# slave_board.net
KiCad netlist of a schematic drawn in EAGLE
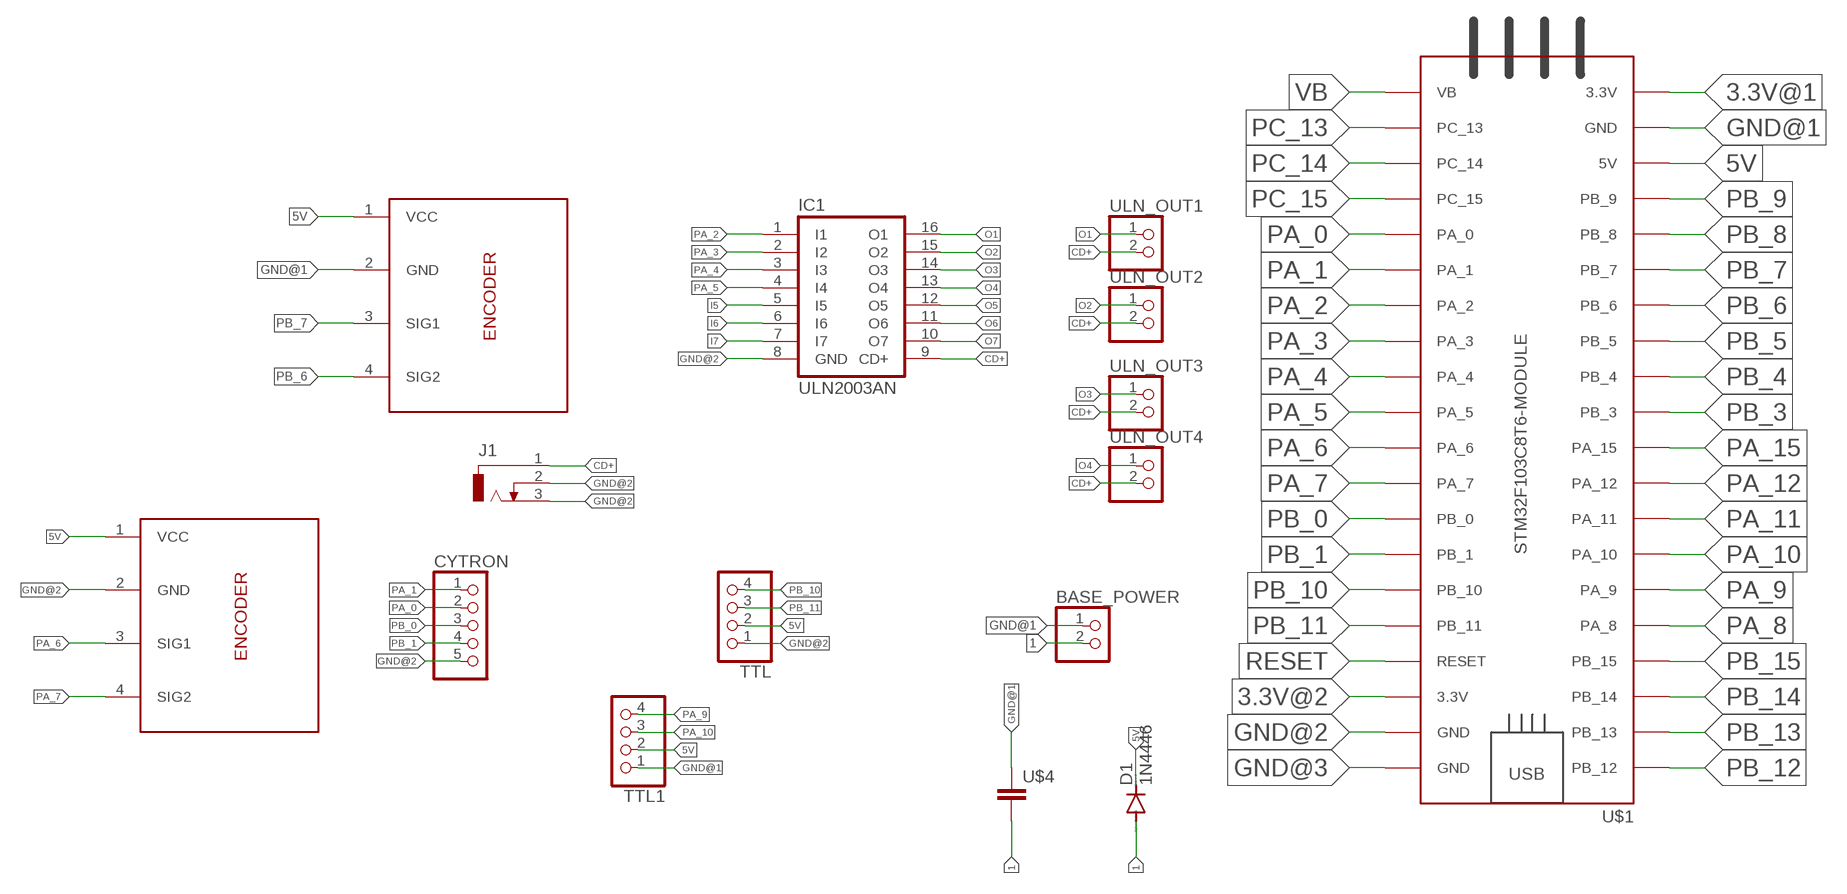
[diagram p0: schematic, sheet 1]

(export (version "E")
  (design (tool "Eeschema 10.0.6"))
  (components
    (comp (ref "BASE_POWER")
      (value "PINHD-2_DATA")
      (footprint "eagle-import:1X02_DATA")
      (libsource (lib "eagle-import") (part "PINHD-2_DATA"))
    )
    (comp (ref "CYTRON")
      (value "PINHD-5_DATA")
      (footprint "eagle-import:1X05_DATA")
      (libsource (lib "eagle-import") (part "PINHD-5_DATA"))
    )
    (comp (ref "D1")
      (value "1N4446")
      (footprint "eagle-import:DO35-10")
      (libsource (lib "eagle-import") (part "1N4446"))
    )
    (comp (ref "IC1")
      (value "ULN2003AN")
      (footprint "eagle-import:DIL16")
      (libsource (lib "eagle-import") (part "ULN2003AN"))
    )
    (comp (ref "J1")
      (value "CON_JACK")
      (footprint "eagle-import:DCJ0303")
      (libsource (lib "eagle-import") (part "CON_JACK"))
    )
    (comp (ref "TTL")
      (value "PINHD-4_DATA")
      (footprint "eagle-import:1X04_DATA")
      (libsource (lib "eagle-import") (part "PINHD-4_DATA"))
    )
    (comp (ref "TTL1")
      (value "PINHD-4_DATA")
      (footprint "eagle-import:1X04_DATA")
      (libsource (lib "eagle-import") (part "PINHD-4_DATA"))
    )
    (comp (ref "U$1")
      (value "STM32F103C8T6-MODULE")
      (footprint "eagle-import:STM32F103C8T6-MODULE")
      (libsource (lib "eagle-import") (part "STM32F103C8T6-MODULE"))
    )
    (comp (ref "U$2")
      (value "ENCODER")
      (footprint "eagle-import:1X04_DATA")
      (libsource (lib "eagle-import") (part "ENCODER"))
    )
    (comp (ref "U$3")
      (value "ENCODER")
      (footprint "eagle-import:1X04_DATA")
      (libsource (lib "eagle-import") (part "ENCODER"))
    )
    (comp (ref "U$4")
      (value "CAPACITOR")
      (footprint "eagle-import:C025-025X050")
      (libsource (lib "eagle-import") (part "CAPACITOR"))
    )
    (comp (ref "ULN_OUT1")
      (value "PINHD-2_DATA")
      (footprint "eagle-import:1X02_DATA")
      (libsource (lib "eagle-import") (part "PINHD-2_DATA"))
    )
    (comp (ref "ULN_OUT2")
      (value "PINHD-2_DATA")
      (footprint "eagle-import:1X02_DATA")
      (libsource (lib "eagle-import") (part "PINHD-2_DATA"))
    )
    (comp (ref "ULN_OUT3")
      (value "PINHD-2_DATA")
      (footprint "eagle-import:1X02_DATA")
      (libsource (lib "eagle-import") (part "PINHD-2_DATA"))
    )
    (comp (ref "ULN_OUT4")
      (value "PINHD-2_DATA")
      (footprint "eagle-import:1X02_DATA")
      (libsource (lib "eagle-import") (part "PINHD-2_DATA"))
    )
  )
  (nets
    (net (code "1") (name "1") (class "Default")
      (node (ref "BASE_POWER") (pin "2") (pinfunction "2_2") (pintype "passive"))
      (node (ref "D1") (pin "A") (pinfunction "A_A") (pintype "passive"))
      (node (ref "U$4") (pin "2") (pinfunction "2_2") (pintype "passive"))
    )
    (net (code "2") (name "3.3V@1") (class "Default")
      (node (ref "U$1") (pin "3.3V_1") (pinfunction "3.3V_3.3V_1") (pintype "bidirectional"))
    )
    (net (code "3") (name "3.3V@2") (class "Default")
      (node (ref "U$1") (pin "3.3V_2") (pinfunction "3.3V_3.3V_2") (pintype "bidirectional"))
    )
    (net (code "4") (name "5V") (class "Default")
      (node (ref "D1") (pin "C") (pinfunction "C_C") (pintype "passive"))
      (node (ref "TTL") (pin "2") (pinfunction "2_2") (pintype "passive"))
      (node (ref "TTL1") (pin "2") (pinfunction "2_2") (pintype "passive"))
      (node (ref "U$1") (pin "5V") (pinfunction "5V_5V") (pintype "bidirectional"))
      (node (ref "U$2") (pin "1") (pinfunction "VCC_1") (pintype "bidirectional"))
      (node (ref "U$3") (pin "1") (pinfunction "VCC_1") (pintype "bidirectional"))
    )
    (net (code "5") (name "CD+") (class "Default")
      (node (ref "IC1") (pin "9") (pinfunction "CD+_9") (pintype "passive"))
      (node (ref "J1") (pin "1") (pinfunction "1_1") (pintype "passive"))
      (node (ref "ULN_OUT1") (pin "2") (pinfunction "2_2") (pintype "passive"))
      (node (ref "ULN_OUT2") (pin "2") (pinfunction "2_2") (pintype "passive"))
      (node (ref "ULN_OUT3") (pin "2") (pinfunction "2_2") (pintype "passive"))
      (node (ref "ULN_OUT4") (pin "2") (pinfunction "2_2") (pintype "passive"))
    )
    (net (code "6") (name "GND@1") (class "Default")
      (node (ref "BASE_POWER") (pin "1") (pinfunction "1_1") (pintype "passive"))
      (node (ref "TTL1") (pin "1") (pinfunction "1_1") (pintype "passive"))
      (node (ref "U$1") (pin "GND_1") (pinfunction "GND_GND_1") (pintype "bidirectional"))
      (node (ref "U$3") (pin "2") (pinfunction "GND_2") (pintype "bidirectional"))
      (node (ref "U$4") (pin "1") (pinfunction "1_1") (pintype "passive"))
    )
    (net (code "7") (name "GND@2") (class "Default")
      (node (ref "CYTRON") (pin "5") (pinfunction "5_5") (pintype "passive"))
      (node (ref "IC1") (pin "8") (pinfunction "GND_8") (pintype "power_in"))
      (node (ref "J1") (pin "2") (pinfunction "2_2") (pintype "passive"))
      (node (ref "J1") (pin "3") (pinfunction "3_3") (pintype "passive"))
      (node (ref "TTL") (pin "1") (pinfunction "1_1") (pintype "passive"))
      (node (ref "U$1") (pin "GND_2") (pinfunction "GND_GND_2") (pintype "bidirectional"))
      (node (ref "U$2") (pin "2") (pinfunction "GND_2") (pintype "bidirectional"))
    )
    (net (code "8") (name "GND@3") (class "Default")
      (node (ref "U$1") (pin "GND_3") (pinfunction "GND_GND_3") (pintype "power_in"))
    )
    (net (code "9") (name "I5") (class "Default")
      (node (ref "IC1") (pin "5") (pinfunction "I5_5") (pintype "input"))
    )
    (net (code "10") (name "I6") (class "Default")
      (node (ref "IC1") (pin "6") (pinfunction "I6_6") (pintype "input"))
    )
    (net (code "11") (name "I7") (class "Default")
      (node (ref "IC1") (pin "7") (pinfunction "I7_7") (pintype "input"))
    )
    (net (code "12") (name "O1") (class "Default")
      (node (ref "IC1") (pin "16") (pinfunction "O1_16") (pintype "open_collector"))
      (node (ref "ULN_OUT1") (pin "1") (pinfunction "1_1") (pintype "passive"))
    )
    (net (code "13") (name "O2") (class "Default")
      (node (ref "IC1") (pin "15") (pinfunction "O2_15") (pintype "open_collector"))
      (node (ref "ULN_OUT2") (pin "1") (pinfunction "1_1") (pintype "passive"))
    )
    (net (code "14") (name "O3") (class "Default")
      (node (ref "IC1") (pin "14") (pinfunction "O3_14") (pintype "open_collector"))
      (node (ref "ULN_OUT3") (pin "1") (pinfunction "1_1") (pintype "passive"))
    )
    (net (code "15") (name "O4") (class "Default")
      (node (ref "IC1") (pin "13") (pinfunction "O4_13") (pintype "open_collector"))
      (node (ref "ULN_OUT4") (pin "1") (pinfunction "1_1") (pintype "passive"))
    )
    (net (code "16") (name "O5") (class "Default")
      (node (ref "IC1") (pin "12") (pinfunction "O5_12") (pintype "open_collector"))
    )
    (net (code "17") (name "O6") (class "Default")
      (node (ref "IC1") (pin "11") (pinfunction "O6_11") (pintype "open_collector"))
    )
    (net (code "18") (name "O7") (class "Default")
      (node (ref "IC1") (pin "10") (pinfunction "O7_10") (pintype "open_collector"))
    )
    (net (code "19") (name "PA_0") (class "Default")
      (node (ref "CYTRON") (pin "2") (pinfunction "2_2") (pintype "passive"))
      (node (ref "U$1") (pin "PA_0") (pinfunction "PA_0_PA_0") (pintype "bidirectional"))
    )
    (net (code "20") (name "PA_1") (class "Default")
      (node (ref "CYTRON") (pin "1") (pinfunction "1_1") (pintype "passive"))
      (node (ref "U$1") (pin "PA_1") (pinfunction "PA_1_PA_1") (pintype "bidirectional"))
    )
    (net (code "21") (name "PA_2") (class "Default")
      (node (ref "IC1") (pin "1") (pinfunction "I1_1") (pintype "input"))
      (node (ref "U$1") (pin "PA_2") (pinfunction "PA_2_PA_2") (pintype "bidirectional"))
    )
    (net (code "22") (name "PA_3") (class "Default")
      (node (ref "IC1") (pin "2") (pinfunction "I2_2") (pintype "input"))
      (node (ref "U$1") (pin "PA_3") (pinfunction "PA_3_PA_3") (pintype "bidirectional"))
    )
    (net (code "23") (name "PA_4") (class "Default")
      (node (ref "IC1") (pin "3") (pinfunction "I3_3") (pintype "input"))
      (node (ref "U$1") (pin "PA_4") (pinfunction "PA_4_PA_4") (pintype "bidirectional"))
    )
    (net (code "24") (name "PA_5") (class "Default")
      (node (ref "IC1") (pin "4") (pinfunction "I4_4") (pintype "input"))
      (node (ref "U$1") (pin "PA_5") (pinfunction "PA_5_PA_5") (pintype "bidirectional"))
    )
    (net (code "25") (name "PA_6") (class "Default")
      (node (ref "U$1") (pin "PA_6") (pinfunction "PA_6_PA_6") (pintype "bidirectional"))
      (node (ref "U$2") (pin "3") (pinfunction "SIG1_3") (pintype "bidirectional"))
    )
    (net (code "26") (name "PA_7") (class "Default")
      (node (ref "U$1") (pin "PA_7") (pinfunction "PA_7_PA_7") (pintype "bidirectional"))
      (node (ref "U$2") (pin "4") (pinfunction "SIG2_4") (pintype "bidirectional"))
    )
    (net (code "27") (name "PA_8") (class "Default")
      (node (ref "U$1") (pin "PA_8") (pinfunction "PA_8_PA_8") (pintype "bidirectional"))
    )
    (net (code "28") (name "PA_9") (class "Default")
      (node (ref "TTL1") (pin "4") (pinfunction "4_4") (pintype "passive"))
      (node (ref "U$1") (pin "PA_9") (pinfunction "PA_9_PA_9") (pintype "bidirectional"))
    )
    (net (code "29") (name "PA_10") (class "Default")
      (node (ref "TTL1") (pin "3") (pinfunction "3_3") (pintype "passive"))
      (node (ref "U$1") (pin "PA_10") (pinfunction "PA_10_PA_10") (pintype "bidirectional"))
    )
    (net (code "30") (name "PA_11") (class "Default")
      (node (ref "U$1") (pin "PA_11") (pinfunction "PA_11_PA_11") (pintype "bidirectional"))
    )
    (net (code "31") (name "PA_12") (class "Default")
      (node (ref "U$1") (pin "PA_12") (pinfunction "PA_12_PA_12") (pintype "bidirectional"))
    )
    (net (code "32") (name "PA_15") (class "Default")
      (node (ref "U$1") (pin "PA_15") (pinfunction "PA_15_PA_15") (pintype "bidirectional"))
    )
    (net (code "33") (name "PB_0") (class "Default")
      (node (ref "CYTRON") (pin "3") (pinfunction "3_3") (pintype "passive"))
      (node (ref "U$1") (pin "PB_0") (pinfunction "PB_0_PB_0") (pintype "bidirectional"))
    )
    (net (code "34") (name "PB_1") (class "Default")
      (node (ref "CYTRON") (pin "4") (pinfunction "4_4") (pintype "passive"))
      (node (ref "U$1") (pin "PB_1") (pinfunction "PB_1_PB_1") (pintype "bidirectional"))
    )
    (net (code "35") (name "PB_3") (class "Default")
      (node (ref "U$1") (pin "PB_3") (pinfunction "PB_3_PB_3") (pintype "bidirectional"))
    )
    (net (code "36") (name "PB_4") (class "Default")
      (node (ref "U$1") (pin "PB_4") (pinfunction "PB_4_PB_4") (pintype "bidirectional"))
    )
    (net (code "37") (name "PB_5") (class "Default")
      (node (ref "U$1") (pin "PB_5") (pinfunction "PB_5_PB_5") (pintype "bidirectional"))
    )
    (net (code "38") (name "PB_6") (class "Default")
      (node (ref "U$1") (pin "PB_6") (pinfunction "PB_6_PB_6") (pintype "bidirectional"))
      (node (ref "U$3") (pin "4") (pinfunction "SIG2_4") (pintype "bidirectional"))
    )
    (net (code "39") (name "PB_7") (class "Default")
      (node (ref "U$1") (pin "PB_7") (pinfunction "PB_7_PB_7") (pintype "bidirectional"))
      (node (ref "U$3") (pin "3") (pinfunction "SIG1_3") (pintype "bidirectional"))
    )
    (net (code "40") (name "PB_8") (class "Default")
      (node (ref "U$1") (pin "PB_8") (pinfunction "PB_8_PB_8") (pintype "bidirectional"))
    )
    (net (code "41") (name "PB_9") (class "Default")
      (node (ref "U$1") (pin "PB_9") (pinfunction "PB_9_PB_9") (pintype "bidirectional"))
    )
    (net (code "42") (name "PB_10") (class "Default")
      (node (ref "TTL") (pin "4") (pinfunction "4_4") (pintype "passive"))
      (node (ref "U$1") (pin "PB_10") (pinfunction "PB_10_PB_10") (pintype "bidirectional"))
    )
    (net (code "43") (name "PB_11") (class "Default")
      (node (ref "TTL") (pin "3") (pinfunction "3_3") (pintype "passive"))
      (node (ref "U$1") (pin "PB_11") (pinfunction "PB_11_PB_11") (pintype "bidirectional"))
    )
    (net (code "44") (name "PB_12") (class "Default")
      (node (ref "U$1") (pin "PB_12") (pinfunction "PB_12_PB_12") (pintype "bidirectional"))
    )
    (net (code "45") (name "PB_13") (class "Default")
      (node (ref "U$1") (pin "PB_13") (pinfunction "PB_13_PB_13") (pintype "bidirectional"))
    )
    (net (code "46") (name "PB_14") (class "Default")
      (node (ref "U$1") (pin "PB_14") (pinfunction "PB_14_PB_14") (pintype "bidirectional"))
    )
    (net (code "47") (name "PB_15") (class "Default")
      (node (ref "U$1") (pin "PB_15") (pinfunction "PB_15_PB_15") (pintype "bidirectional"))
    )
    (net (code "48") (name "PC_13") (class "Default")
      (node (ref "U$1") (pin "PC_13") (pinfunction "PC_13_PC_13") (pintype "bidirectional"))
    )
    (net (code "49") (name "PC_14") (class "Default")
      (node (ref "U$1") (pin "PC_14") (pinfunction "PC_14_PC_14") (pintype "bidirectional"))
    )
    (net (code "50") (name "PC_15") (class "Default")
      (node (ref "U$1") (pin "PC_15") (pinfunction "PC_15_PC_15") (pintype "bidirectional"))
    )
    (net (code "51") (name "RESET") (class "Default")
      (node (ref "U$1") (pin "RESET") (pinfunction "RESET_RESET") (pintype "bidirectional"))
    )
    (net (code "52") (name "VB") (class "Default")
      (node (ref "U$1") (pin "VB") (pinfunction "VB_VB") (pintype "bidirectional"))
    )
  )
)
